# dual_supply.net
KiCad netlist of a schematic drawn in EAGLE
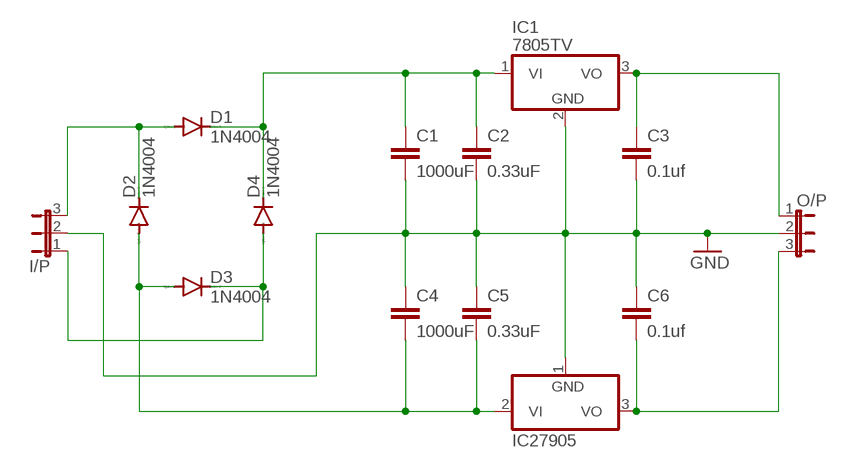
[diagram p0: schematic, sheet 1]

(export (version "E")
  (design (tool "Eeschema 10.0.6"))
  (components
    (comp (ref "C1")
      (value "1000uF")
      (footprint "eagle-import:C2.5-3")
      (libsource (lib "eagle-import") (part "C2,5-3"))
    )
    (comp (ref "C2")
      (value "0.33uF")
      (footprint "eagle-import:C2.5-3")
      (libsource (lib "eagle-import") (part "C2,5-3"))
    )
    (comp (ref "C3")
      (value "0.1uf")
      (footprint "eagle-import:C2.5-3")
      (libsource (lib "eagle-import") (part "C2,5-3"))
    )
    (comp (ref "C4")
      (value "1000uF")
      (footprint "eagle-import:C2.5-3")
      (libsource (lib "eagle-import") (part "C2,5-3"))
    )
    (comp (ref "C5")
      (value "0.33uF")
      (footprint "eagle-import:C2.5-3")
      (libsource (lib "eagle-import") (part "C2,5-3"))
    )
    (comp (ref "C6")
      (value "0.1uf")
      (footprint "eagle-import:C2.5-3")
      (libsource (lib "eagle-import") (part "C2,5-3"))
    )
    (comp (ref "D1")
      (value "1N4004")
      (footprint "eagle-import:DO41-10")
      (libsource (lib "eagle-import") (part "1N4004"))
    )
    (comp (ref "D2")
      (value "1N4004")
      (footprint "eagle-import:DO41-10")
      (libsource (lib "eagle-import") (part "1N4004"))
    )
    (comp (ref "D3")
      (value "1N4004")
      (footprint "eagle-import:DO41-10")
      (libsource (lib "eagle-import") (part "1N4004"))
    )
    (comp (ref "D4")
      (value "1N4004")
      (footprint "eagle-import:DO41-10")
      (libsource (lib "eagle-import") (part "1N4004"))
    )
    (comp (ref "I/P")
      (value "JP2E")
      (footprint "eagle-import:JP2")
      (libsource (lib "eagle-import") (part "JP2E"))
    )
    (comp (ref "IC1")
      (value "7805TV")
      (footprint "eagle-import:TO220V")
      (libsource (lib "eagle-import") (part "78TV05"))
    )
    (comp (ref "IC27905")
      (value "7905T")
      (footprint "eagle-import:TO220H")
      (libsource (lib "eagle-import") (part "79T05"))
    )
    (comp (ref "O/P")
      (value "JP2E")
      (footprint "eagle-import:JP2")
      (libsource (lib "eagle-import") (part "JP2E"))
    )
  )
  (nets
    (net (code "1") (name "GND") (class "Default")
      (node (ref "C1") (pin "2") (pinfunction "2_2") (pintype "passive"))
      (node (ref "C2") (pin "2") (pinfunction "2_2") (pintype "passive"))
      (node (ref "C3") (pin "2") (pinfunction "2_2") (pintype "passive"))
      (node (ref "C4") (pin "1") (pinfunction "1_1") (pintype "passive"))
      (node (ref "C5") (pin "1") (pinfunction "1_1") (pintype "passive"))
      (node (ref "C6") (pin "1") (pinfunction "1_1") (pintype "passive"))
      (node (ref "I/P") (pin "2") (pinfunction "2_2") (pintype "passive"))
      (node (ref "IC1") (pin "2") (pinfunction "GND_2") (pintype "passive"))
      (node (ref "IC27905") (pin "1") (pinfunction "GND_1") (pintype "passive"))
      (node (ref "O/P") (pin "2") (pinfunction "2_2") (pintype "passive"))
    )
    (net (code "2") (name "Net-(D1-PadA)") (class "Default")
      (node (ref "D1") (pin "A") (pinfunction "A_A") (pintype "passive"))
      (node (ref "D2") (pin "C") (pinfunction "C_C") (pintype "passive"))
      (node (ref "I/P") (pin "3") (pinfunction "3_3") (pintype "passive"))
    )
    (net (code "3") (name "Net-(D3-PadC)") (class "Default")
      (node (ref "D3") (pin "C") (pinfunction "C_C") (pintype "passive"))
      (node (ref "D4") (pin "A") (pinfunction "A_A") (pintype "passive"))
      (node (ref "I/P") (pin "1") (pinfunction "1_1") (pintype "passive"))
    )
    (net (code "4") (name "Net-(IC1-VI)") (class "Default")
      (node (ref "C1") (pin "1") (pinfunction "1_1") (pintype "passive"))
      (node (ref "C2") (pin "1") (pinfunction "1_1") (pintype "passive"))
      (node (ref "D1") (pin "C") (pinfunction "C_C") (pintype "passive"))
      (node (ref "D4") (pin "C") (pinfunction "C_C") (pintype "passive"))
      (node (ref "IC1") (pin "1") (pinfunction "VI_1") (pintype "input"))
    )
    (net (code "5") (name "Net-(IC1-VO)") (class "Default")
      (node (ref "C3") (pin "1") (pinfunction "1_1") (pintype "passive"))
      (node (ref "IC1") (pin "3") (pinfunction "VO_3") (pintype "passive"))
      (node (ref "O/P") (pin "1") (pinfunction "1_1") (pintype "passive"))
    )
    (net (code "6") (name "Net-(IC27905-VI)") (class "Default")
      (node (ref "C4") (pin "2") (pinfunction "2_2") (pintype "passive"))
      (node (ref "C5") (pin "2") (pinfunction "2_2") (pintype "passive"))
      (node (ref "D2") (pin "A") (pinfunction "A_A") (pintype "passive"))
      (node (ref "D3") (pin "A") (pinfunction "A_A") (pintype "passive"))
      (node (ref "IC27905") (pin "2") (pinfunction "VI_2") (pintype "input"))
    )
    (net (code "7") (name "Net-(IC27905-VO)") (class "Default")
      (node (ref "C6") (pin "2") (pinfunction "2_2") (pintype "passive"))
      (node (ref "IC27905") (pin "3") (pinfunction "VO_3") (pintype "passive"))
      (node (ref "O/P") (pin "3") (pinfunction "3_3") (pintype "passive"))
    )
  )
)
